# neck_assembly.net
KiCad netlist of a schematic drawn in EAGLE
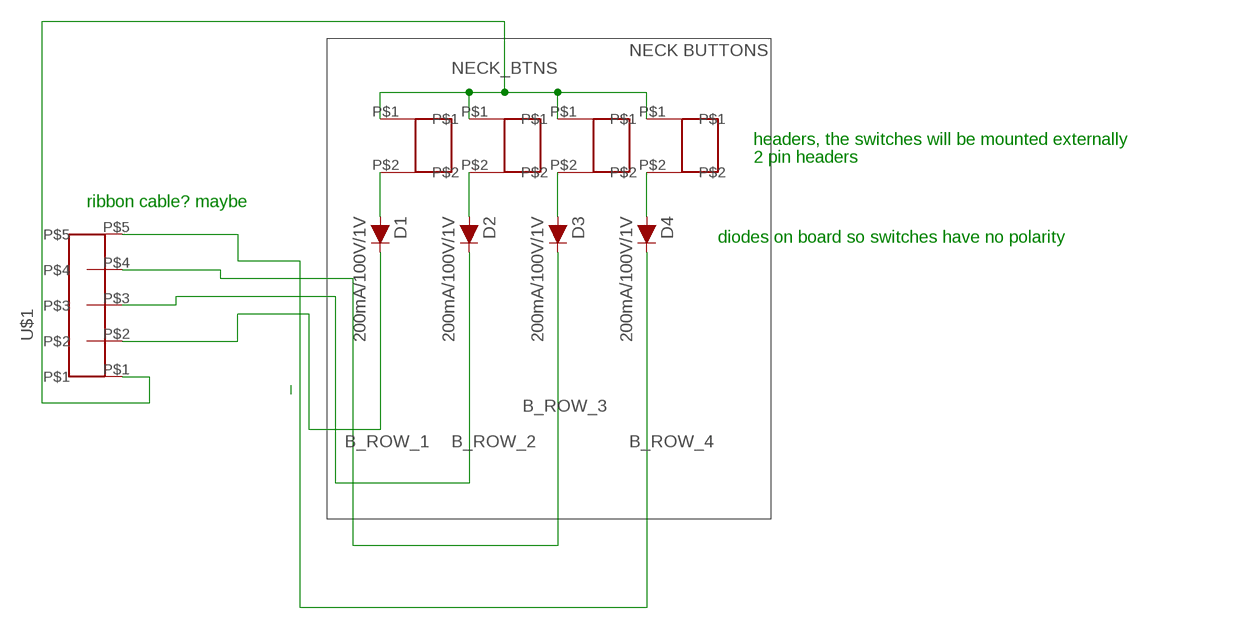
[diagram p0: schematic, sheet 1]

(export (version "E")
  (design (tool "Eeschema 10.0.6"))
  (components
    (comp (ref "B1")
      (value "2-PIN-HEADER")
      (footprint "eagle-import:2-PIN-HEADER")
      (libsource (lib "eagle-import") (part "2-PIN-HEADER"))
    )
    (comp (ref "B2")
      (value "2-PIN-HEADER")
      (footprint "eagle-import:2-PIN-HEADER")
      (libsource (lib "eagle-import") (part "2-PIN-HEADER"))
    )
    (comp (ref "B3")
      (value "2-PIN-HEADER")
      (footprint "eagle-import:2-PIN-HEADER")
      (libsource (lib "eagle-import") (part "2-PIN-HEADER"))
    )
    (comp (ref "B4")
      (value "2-PIN-HEADER")
      (footprint "eagle-import:2-PIN-HEADER")
      (libsource (lib "eagle-import") (part "2-PIN-HEADER"))
    )
    (comp (ref "D1")
      (value "200mA/100V/1V")
      (footprint "eagle-import:DIODE-1N4148")
      (libsource (lib "eagle-import") (part "DIODE-1N4148"))
    )
    (comp (ref "D2")
      (value "200mA/100V/1V")
      (footprint "eagle-import:DIODE-1N4148")
      (libsource (lib "eagle-import") (part "DIODE-1N4148"))
    )
    (comp (ref "D3")
      (value "200mA/100V/1V")
      (footprint "eagle-import:DIODE-1N4148")
      (libsource (lib "eagle-import") (part "DIODE-1N4148"))
    )
    (comp (ref "D4")
      (value "200mA/100V/1V")
      (footprint "eagle-import:DIODE-1N4148")
      (libsource (lib "eagle-import") (part "DIODE-1N4148"))
    )
    (comp (ref "U$1")
      (value "5-PIN-HEADER")
      (footprint "eagle-import:5-PIN-HEADER")
      (libsource (lib "eagle-import") (part "5-PIN-HEADER"))
    )
  )
  (nets
    (net (code "1") (name "/B_ROW_1") (class "Default")
      (node (ref "D1") (pin "C") (pinfunction "C_C") (pintype "passive"))
      (node (ref "U$1") (pin "P$2") (pinfunction "P$2_P$2") (pintype "bidirectional"))
    )
    (net (code "2") (name "/B_ROW_2") (class "Default")
      (node (ref "D2") (pin "C") (pinfunction "C_C") (pintype "passive"))
      (node (ref "U$1") (pin "P$3") (pinfunction "P$3_P$3") (pintype "bidirectional"))
    )
    (net (code "3") (name "/B_ROW_3") (class "Default")
      (node (ref "D3") (pin "C") (pinfunction "C_C") (pintype "passive"))
      (node (ref "U$1") (pin "P$4") (pinfunction "P$4_P$4") (pintype "bidirectional"))
    )
    (net (code "4") (name "/B_ROW_4") (class "Default")
      (node (ref "D4") (pin "C") (pinfunction "C_C") (pintype "passive"))
      (node (ref "U$1") (pin "P$5") (pinfunction "P$5_P$5") (pintype "bidirectional"))
    )
    (net (code "5") (name "/NECK_BTNS") (class "Default")
      (node (ref "B1") (pin "P$1") (pinfunction "P$1_P$1") (pintype "bidirectional"))
      (node (ref "B2") (pin "P$1") (pinfunction "P$1_P$1") (pintype "bidirectional"))
      (node (ref "B3") (pin "P$1") (pinfunction "P$1_P$1") (pintype "bidirectional"))
      (node (ref "B4") (pin "P$1") (pinfunction "P$1_P$1") (pintype "bidirectional"))
      (node (ref "U$1") (pin "P$1") (pinfunction "P$1_P$1") (pintype "bidirectional"))
    )
    (net (code "6") (name "Net-(B1-PadP$2)") (class "Default")
      (node (ref "B1") (pin "P$2") (pinfunction "P$2_P$2") (pintype "bidirectional"))
      (node (ref "D1") (pin "A") (pinfunction "A_A") (pintype "passive"))
    )
    (net (code "7") (name "Net-(B2-PadP$2)") (class "Default")
      (node (ref "B2") (pin "P$2") (pinfunction "P$2_P$2") (pintype "bidirectional"))
      (node (ref "D2") (pin "A") (pinfunction "A_A") (pintype "passive"))
    )
    (net (code "8") (name "Net-(B3-PadP$2)") (class "Default")
      (node (ref "B3") (pin "P$2") (pinfunction "P$2_P$2") (pintype "bidirectional"))
      (node (ref "D3") (pin "A") (pinfunction "A_A") (pintype "passive"))
    )
    (net (code "9") (name "Net-(B4-PadP$2)") (class "Default")
      (node (ref "B4") (pin "P$2") (pinfunction "P$2_P$2") (pintype "bidirectional"))
      (node (ref "D4") (pin "A") (pinfunction "A_A") (pintype "passive"))
    )
  )
)
